# breakout-wson6-sot23-5.net
KiCad netlist of a schematic drawn in EAGLE
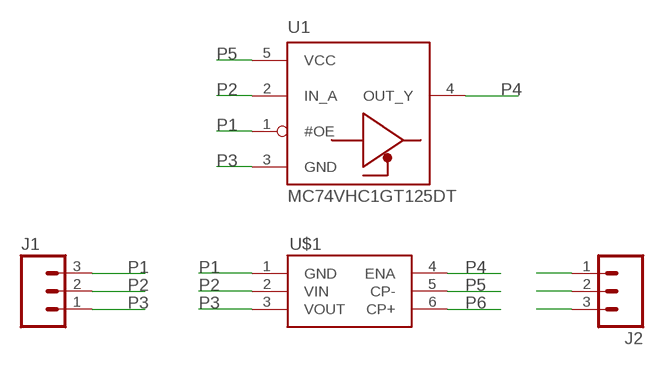
[diagram p0: schematic, sheet 1]

(export (version "E")
  (design (tool "Eeschema 10.0.6"))
  (components
    (comp (ref "J1")
      (value "M03LOCK")
      (footprint "eagle-import:1X03_LOCK")
      (libsource (lib "eagle-import") (part "M03LOCK"))
    )
    (comp (ref "J2")
      (value "M03LOCK")
      (footprint "eagle-import:1X03_LOCK")
      (libsource (lib "eagle-import") (part "M03LOCK"))
    )
    (comp (ref "U$1")
      (value "TPS60150")
      (footprint "eagle-import:WSON6")
      (libsource (lib "eagle-import") (part "TPS60150"))
    )
    (comp (ref "U1")
      (value "MC74VHC1GT125DT")
      (footprint "eagle-import:SOT23-5")
      (libsource (lib "eagle-import") (part "MC74VHC1GT125DT"))
    )
  )
  (nets
    (net (code "1") (name "/P1") (class "Default")
      (node (ref "J1") (pin "3") (pinfunction "3_3") (pintype "passive"))
      (node (ref "U$1") (pin "1") (pinfunction "GND_1") (pintype "power_in"))
      (node (ref "U1") (pin "1") (pinfunction "#OE_1") (pintype "input"))
    )
    (net (code "2") (name "/P2") (class "Default")
      (node (ref "J1") (pin "2") (pinfunction "2_2") (pintype "passive"))
      (node (ref "U$1") (pin "2") (pinfunction "VIN_2") (pintype "power_in"))
      (node (ref "U1") (pin "2") (pinfunction "IN_A_2") (pintype "bidirectional"))
    )
    (net (code "3") (name "/P3") (class "Default")
      (node (ref "J1") (pin "1") (pinfunction "1_1") (pintype "passive"))
      (node (ref "U$1") (pin "3") (pinfunction "VOUT_3") (pintype "power_in"))
      (node (ref "U1") (pin "3") (pinfunction "GND_3") (pintype "power_in"))
    )
    (net (code "4") (name "/P4") (class "Default")
      (node (ref "J2") (pin "3") (pinfunction "3_3") (pintype "passive"))
      (node (ref "U$1") (pin "4") (pinfunction "ENA_4") (pintype "input"))
      (node (ref "U1") (pin "4") (pinfunction "OUT_Y_4") (pintype "bidirectional"))
    )
    (net (code "5") (name "/P5") (class "Default")
      (node (ref "J2") (pin "2") (pinfunction "2_2") (pintype "passive"))
      (node (ref "U$1") (pin "5") (pinfunction "CP-_5") (pintype "bidirectional"))
      (node (ref "U1") (pin "5") (pinfunction "VCC_5") (pintype "power_in"))
    )
    (net (code "6") (name "/P6") (class "Default")
      (node (ref "J2") (pin "1") (pinfunction "1_1") (pintype "passive"))
      (node (ref "U$1") (pin "6") (pinfunction "CP+_6") (pintype "bidirectional"))
    )
  )
)
